# 10_MIPI_LCD_TX2.net
KiCad netlist of a schematic drawn in Altium Designer
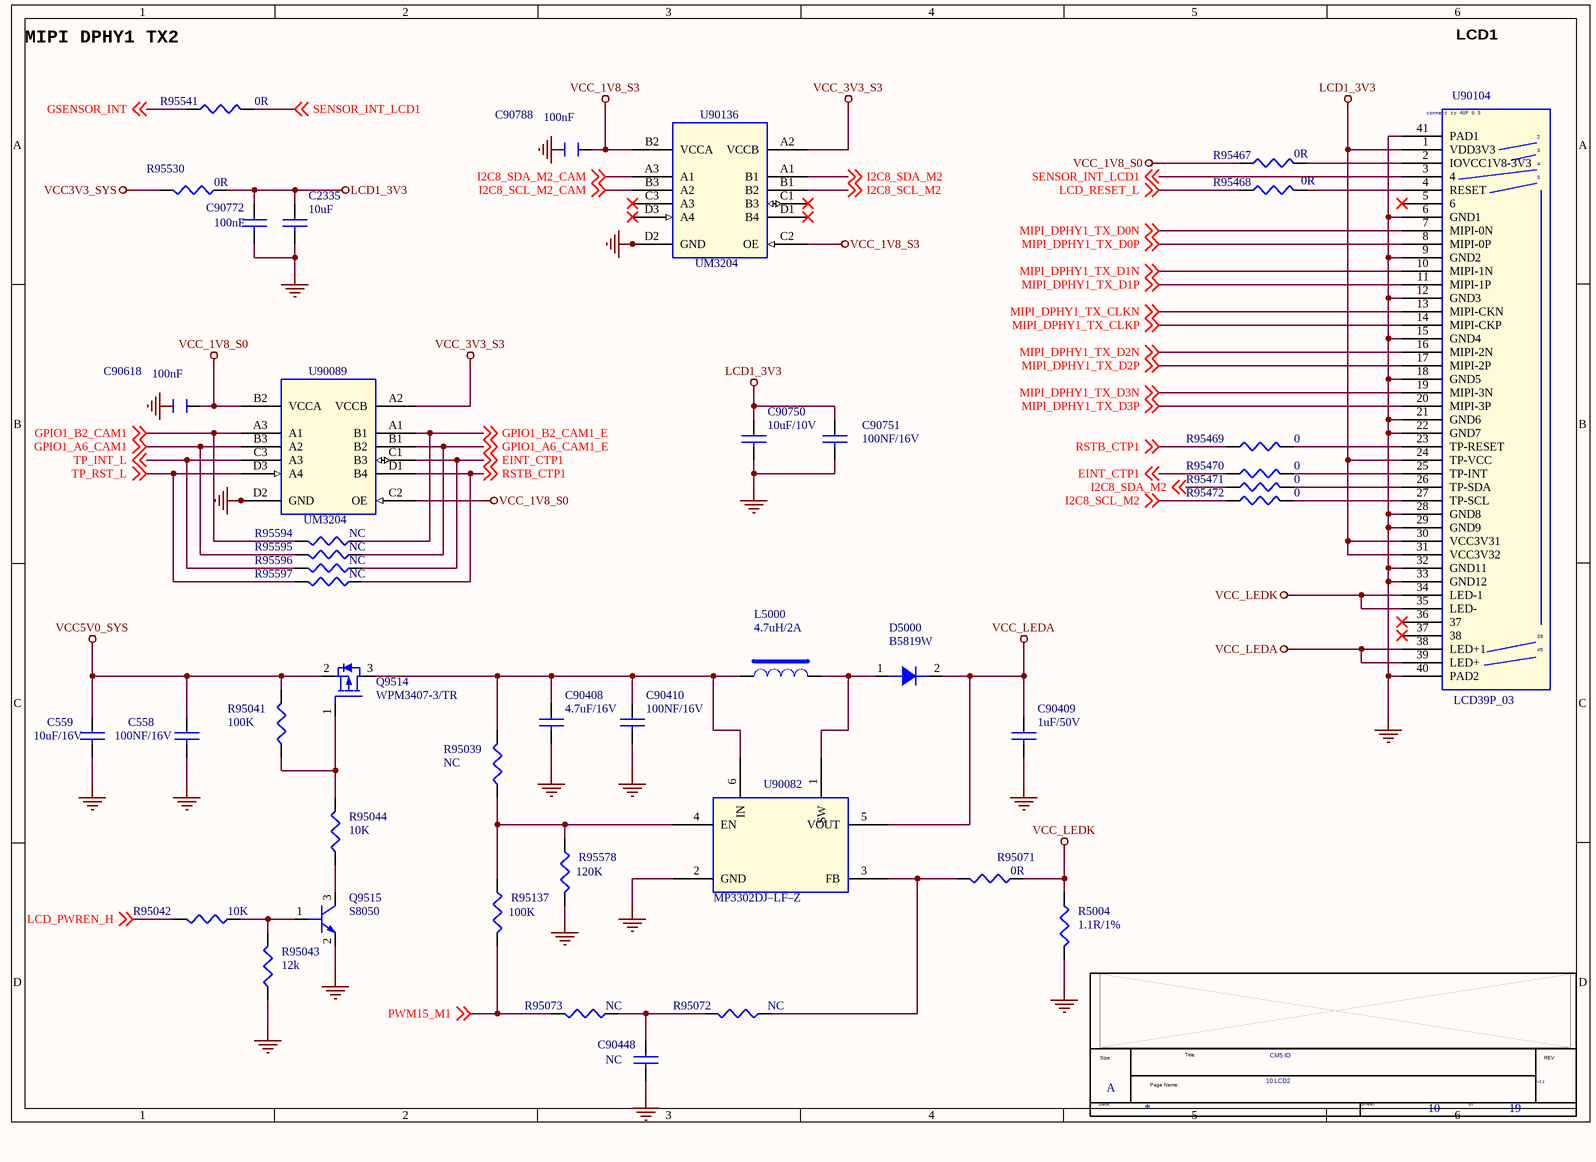
[diagram p0: 10_MIPI_LCD_TX2.SchDoc]

(export (version "E")
  (design (tool "Eeschema 10.0.6"))
  (components
    (comp (ref "*")
      (value "radxa_1010")
      (fields
        (field (name "DOC") "10.LCD2")
        (field (name "REVCODE") "V2.2")
        (field (name "TITLE") "CM5 IO")
        (field (name "PAGE SIZE") "A")
        (field (name "PAGE NUMBER") "10")
        (field (name "PAGE COUNT") "19")
      )
      (libsource (lib "*") (part "radxa_1010"))
    )
    (comp (ref "C558")
      (value "100NF/16V")
      (footprint "C0402")
      (description "cap,100.00nF,+/-10%,16V,X5R,C0402")
      (fields
        (field (name "VOLTAGE") "16V")
        (field (name "TOLERANCE") "10%")
        (field (name "CREATED BY") "JJJ")
      )
      (libsource (lib "*") (part "CAP NP_0_Dup2"))
    )
    (comp (ref "C559")
      (value "10uF/16V")
      (footprint "C0603")
      (description "cap,10.00uF,+/-10%,10V,X5R,C0603")
      (fields
        (field (name "VOLTAGE") "10V")
        (field (name "MANUFACTURER") "TDK")
        (field (name "CREATED BY") "JJJ")
      )
      (libsource (lib "*") (part "CAP NP_0_Dup2"))
    )
    (comp (ref "C2335")
      (value "10uF")
      (footprint "C0603")
      (description "cap,10.00uF,+/-10%,10V,X5R,C0603")
      (fields
        (field (name "VOLTAGE") "10V")
        (field (name "TOLERANCE") "10%")
        (field (name "CREATED BY") "JJJ")
      )
      (libsource (lib "*") (part "CAP NP_0_Dup2"))
    )
    (comp (ref "C90408")
      (value "4.7uF/16V")
      (footprint "C0603")
      (description "cap,4.70uF,+/-10%,10V,X5R,C0603")
      (fields
        (field (name "VOLTAGE") "10V")
        (field (name "TOLERANCE") "10%")
        (field (name "CREATED BY") "JJJ")
      )
      (libsource (lib "*") (part "CAP NP_0_Dup2"))
    )
    (comp (ref "C90409")
      (value "1uF/50V")
      (footprint "C0603")
      (description "cap,2.20uF,+/-10%,35V,X5R,C0603")
      (fields
        (field (name "VOLTAGE") "35V")
        (field (name "TOLERANCE") "10%")
        (field (name "CREATED BY") "JJJ")
      )
      (libsource (lib "*") (part "CAP NP_0_Dup2"))
    )
    (comp (ref "C90410")
      (value "100NF/16V")
      (footprint "C0402")
      (description "cap,100.00nF,+/-10%,16V,X5R,C0402")
      (fields
        (field (name "VOLTAGE") "16V")
        (field (name "TOLERANCE") "10%")
        (field (name "CREATED BY") "JJJ")
      )
      (libsource (lib "*") (part "CAP NP_0_Dup2"))
    )
    (comp (ref "C90448")
      (value "NC")
      (footprint "C0402")
      (description "cap,100.00nF,+/-10%,16V,X5R,C0402")
      (fields
        (field (name "VOLTAGE") "16V")
        (field (name "TOLERANCE") "10%")
        (field (name "CREATED BY") "JJJ")
      )
      (libsource (lib "*") (part "CAP NP_0_Dup2"))
    )
    (comp (ref "C90618") (value "100nF") (footprint "C0402") (libsource (lib "*") (part "CAPACITOR_0")))
    (comp (ref "C90750")
      (value "10uF/10V")
      (footprint "C0603")
      (description "cap,10.00uF,+/-10%,10V,X5R,C0603")
      (fields
        (field (name "VOLTAGE") "10V")
        (field (name "TOLERANCE") "10%")
        (field (name "CREATED BY") "JJJ")
      )
      (libsource (lib "*") (part "CAP NP_0_Dup2"))
    )
    (comp (ref "C90751")
      (value "100NF/16V")
      (footprint "C0402")
      (description "cap,100.00nF,+/-10%,16V,X5R,C0402")
      (fields
        (field (name "VOLTAGE") "16V")
        (field (name "MANUFACTURER") "TDK")
        (field (name "CREATED BY") "JJJ")
      )
      (libsource (lib "*") (part "CAP NP_0_Dup2"))
    )
    (comp (ref "C90772")
      (value "100nF")
      (footprint "C0402")
      (description "cap,100.00nF,+/-10%,16V,X5R,C0402")
      (fields
        (field (name "VOLTAGE") "16V")
        (field (name "TOLERANCE") "10%")
        (field (name "CREATED BY") "JJJ")
      )
      (libsource (lib "*") (part "CAP NP_0_Dup2"))
    )
    (comp (ref "C90788") (value "100nF") (footprint "C0402") (libsource (lib "*") (part "CAPACITOR_0")))
    (comp (ref "D5000")
      (value "B5819W")
      (footprint "SOD_123")
      (description "Schottky Barrier，SS32 DO214AC")
      (fields (field (name "MANUFACTURER") "星海") (field (name "CREATED BY") "JJJ"))
      (libsource (lib "*") (part "DIODE_Dup1"))
    )
    (comp (ref "L5000")
      (value "4.7uH/2A")
      (footprint "IND-303015")
      (description "Power Inductor,4.7uH,0.2,IND_404030")
      (fields
        (field (name "TOLERANCE") "20%")
        (field (name "MANUFACTURER") "sunlord")
        (field (name "CREATED BY") "YTL")
      )
      (libsource (lib "*") (part "INDUCTORS OF FERRITE_Dup1"))
    )
    (comp (ref "Q9514")
      (value "WPM3407-3/TR")
      (footprint "SOT23")
      (description "PMOS,WPM3407-3/TR,SOT_23,Id=4.4A,Vds=30V")
      (fields (field (name "MANUFACTURER") "WillSemi(韦尔半导体)") (field (name "CREATED BY") "JJJ"))
      (libsource (lib "*") (part "MOSFET P"))
    )
    (comp (ref "Q9515")
      (value "S8050")
      (footprint "SOT_23")
      (description "S8050,SOT23")
      (fields (field (name "MANUFACTURER") "长电") (field (name "CREATED BY") "JJJ"))
      (libsource (lib "*") (part "NPN"))
    )
    (comp (ref "R5004")
      (value "1.1R/1%")
      (footprint "R0402")
      (description "通用厚膜电阻,3R9,+/-5%,R1206,1/4W.")
      (fields
        (field (name "TOLERANCE") "5%")
        (field (name "MANUFACTURER") "YAGEO")
        (field (name "CREATED BY") "YTL")
      )
      (libsource (lib "*") (part "RESISTOR_1_Dup1"))
    )
    (comp (ref "R95039")
      (value "NC")
      (footprint "R0402")
      (description "通用厚膜电阻,27K,+/-5%,R0402,1/16W.")
      (fields
        (field (name "TOLERANCE") "5%")
        (field (name "MANUFACTURER") "YAGEO")
        (field (name "CREATED BY") "YTL")
      )
      (libsource (lib "*") (part "RESISTOR_1_Dup1"))
    )
    (comp (ref "R95041")
      (value "100K")
      (footprint "R0402")
      (description "通用厚膜电阻,10K,+/-5%,R0402,1/16W.")
      (fields
        (field (name "TOLERANCE") "5%")
        (field (name "MANUFACTURER") "YAGEO")
        (field (name "CREATED BY") "YTL")
      )
      (libsource (lib "*") (part "RESISTOR_1_Dup1"))
    )
    (comp (ref "R95042")
      (value "10K")
      (footprint "R0402")
      (description "通用厚膜电阻,10K,+/-5%,R0402,1/16W.")
      (fields
        (field (name "TOLERANCE") "5%")
        (field (name "MANUFACTURER") "YAGEO")
        (field (name "CREATED BY") "YTL")
      )
      (libsource (lib "*") (part "RESISTOR_1_Dup1"))
    )
    (comp (ref "R95043")
      (value "12k")
      (footprint "R0402")
      (description "通用厚膜电阻,20K,+/-5%,R0402,1/16W.")
      (fields
        (field (name "TOLERANCE") "5%")
        (field (name "MANUFACTURER") "YAGEO")
        (field (name "CREATED BY") "YTL")
      )
      (libsource (lib "*") (part "RESISTOR_1_Dup1"))
    )
    (comp (ref "R95044")
      (value "10K")
      (footprint "R0402")
      (description "通用厚膜电阻,10K,+/-5%,R0402,1/16W.")
      (fields
        (field (name "TOLERANCE") "5%")
        (field (name "MANUFACTURER") "YAGEO")
        (field (name "CREATED BY") "YTL")
      )
      (libsource (lib "*") (part "RESISTOR_1_Dup1"))
    )
    (comp (ref "R95071")
      (value "0R")
      (footprint "R0402")
      (description "通用厚膜电阻,27K,+/-5%,R0402,1/16W.")
      (fields
        (field (name "TOLERANCE") "5%")
        (field (name "MANUFACTURER") "YAGEO")
        (field (name "CREATED BY") "YTL")
      )
      (libsource (lib "*") (part "RESISTOR_1_Dup1"))
    )
    (comp (ref "R95072")
      (value "NC")
      (footprint "R0402")
      (description "通用厚膜电阻,27K,+/-5%,R0402,1/16W.")
      (fields
        (field (name "TOLERANCE") "5%")
        (field (name "MANUFACTURER") "YAGEO")
        (field (name "CREATED BY") "YTL")
      )
      (libsource (lib "*") (part "RESISTOR_1_Dup1"))
    )
    (comp (ref "R95073")
      (value "NC")
      (footprint "R0402")
      (description "通用厚膜电阻,27K,+/-5%,R0402,1/16W.")
      (fields
        (field (name "TOLERANCE") "5%")
        (field (name "MANUFACTURER") "YAGEO")
        (field (name "CREATED BY") "YTL")
      )
      (libsource (lib "*") (part "RESISTOR_1_Dup1"))
    )
    (comp (ref "R95137")
      (value "100K")
      (footprint "R0402")
      (description "通用厚膜电阻,27K,+/-5%,R0402,1/16W.")
      (fields
        (field (name "TOLERANCE") "5%")
        (field (name "MANUFACTURER") "YAGEO")
        (field (name "CREATED BY") "YTL")
      )
      (libsource (lib "*") (part "RESISTOR_1_Dup1"))
    )
    (comp (ref "R95467")
      (value "0R")
      (footprint "R0402")
      (description "通用厚膜电阻,100K,+/-5%,R0402,1/16W.")
      (fields
        (field (name "TOLERANCE") "5%")
        (field (name "MANUFACTURER") "YAGEO")
        (field (name "CREATED BY") "YTL")
      )
      (libsource (lib "*") (part "RESISTOR_1_Dup1"))
    )
    (comp (ref "R95468")
      (value "0R")
      (footprint "R0402")
      (description "通用厚膜电阻,100K,+/-5%,R0402,1/16W.")
      (fields
        (field (name "TOLERANCE") "5%")
        (field (name "MANUFACTURER") "YAGEO")
        (field (name "CREATED BY") "YTL")
      )
      (libsource (lib "*") (part "RESISTOR_1_Dup1"))
    )
    (comp (ref "R95469") (value "0") (footprint "R0201") (libsource (lib "*") (part "R / 0 / ohm / 0201_0")))
    (comp (ref "R95470") (value "0") (footprint "R0201") (libsource (lib "*") (part "R / 0 / ohm / 0201_0")))
    (comp (ref "R95471") (value "0") (footprint "R0201") (libsource (lib "*") (part "R / 0 / ohm / 0201_0")))
    (comp (ref "R95472") (value "0") (footprint "R0201") (libsource (lib "*") (part "R / 0 / ohm / 0201_0")))
    (comp (ref "R95530")
      (value "0R")
      (footprint "R0402")
      (description "通用厚膜电阻,10K,+/-5%,R0402,1/16W.")
      (fields
        (field (name "TOLERANCE") "5%")
        (field (name "MANUFACTURER") "YAGEO")
        (field (name "CREATED BY") "YTL")
      )
      (libsource (lib "*") (part "RESISTOR_1_Dup1"))
    )
    (comp (ref "R95541")
      (value "0R")
      (footprint "R0402")
      (description "通用厚膜电阻,10K,+/-5%,R0402,1/16W.")
      (fields
        (field (name "TOLERANCE") "5%")
        (field (name "MANUFACTURER") "YAGEO")
        (field (name "CREATED BY") "YTL")
      )
      (libsource (lib "*") (part "RESISTOR_1_Dup1"))
    )
    (comp (ref "R95578")
      (value "120K")
      (footprint "R0402")
      (description "通用厚膜电阻,27K,+/-5%,R0402,1/16W.")
      (fields
        (field (name "TOLERANCE") "5%")
        (field (name "MANUFACTURER") "YAGEO")
        (field (name "CREATED BY") "YTL")
      )
      (libsource (lib "*") (part "RESISTOR_1_Dup1"))
    )
    (comp (ref "R95594")
      (value "NC")
      (footprint "R0402")
      (description "通用厚膜电阻,10K,+/-5%,R0402,1/16W.")
      (fields
        (field (name "TOLERANCE") "5%")
        (field (name "MANUFACTURER") "YAGEO")
        (field (name "CREATED BY") "YTL")
      )
      (libsource (lib "*") (part "RESISTOR_1_Dup1"))
    )
    (comp (ref "R95595")
      (value "NC")
      (footprint "R0402")
      (description "通用厚膜电阻,10K,+/-5%,R0402,1/16W.")
      (fields
        (field (name "TOLERANCE") "5%")
        (field (name "MANUFACTURER") "YAGEO")
        (field (name "CREATED BY") "YTL")
      )
      (libsource (lib "*") (part "RESISTOR_1_Dup1"))
    )
    (comp (ref "R95596")
      (value "NC")
      (footprint "R0402")
      (description "通用厚膜电阻,10K,+/-5%,R0402,1/16W.")
      (fields
        (field (name "TOLERANCE") "5%")
        (field (name "MANUFACTURER") "YAGEO")
        (field (name "CREATED BY") "YTL")
      )
      (libsource (lib "*") (part "RESISTOR_1_Dup1"))
    )
    (comp (ref "R95597")
      (value "NC")
      (footprint "R0402")
      (description "通用厚膜电阻,10K,+/-5%,R0402,1/16W.")
      (fields
        (field (name "TOLERANCE") "5%")
        (field (name "MANUFACTURER") "YAGEO")
        (field (name "CREATED BY") "YTL")
      )
      (libsource (lib "*") (part "RESISTOR_1_Dup1"))
    )
    (comp (ref "U90082")
      (value "MP3302DJ–LF–Z")
      (footprint "sot23-6")
      (libsource (lib "*") (part "MP3302_0"))
    )
    (comp (ref "U90089")
      (value "UM3204")
      (footprint "CSP-12")
      (description "4-bit Bi-directional Level Shifter  UM3204H")
      (fields (field (name "PART NUMBER") "PI4ULS5V104GAEX"))
      (libsource (lib "*") (part "MP2610_0"))
    )
    (comp (ref "U90104")
      (value "LCD39P_03")
      (footprint "LCD39PIN-ok")
      (libsource (lib "*") (part "LCD39P_03"))
    )
    (comp (ref "U90136")
      (value "UM3204")
      (footprint "CSP-12")
      (description "4-bit Bi-directional Level Shifter  UM3204H")
      (fields (field (name "PART NUMBER") "PI4ULS5V104GAEX"))
      (libsource (lib "*") (part "MP2610_0"))
    )
  )
  (nets
    (net (code "1") (name "EINT_CTP1") (class "Default")
      (node (ref "R95470") (pin "1") (pinfunction "1_1") (pintype "passive"))
      (node (ref "R95596") (pin "2") (pinfunction "2_2") (pintype "passive"))
      (node (ref "U90089") (pin "C1") (pinfunction "B3_C1") (pintype "bidirectional"))
    )
    (net (code "2") (name "GND") (class "Default")
      (node (ref "C2335") (pin "2") (pinfunction "2_2") (pintype "passive"))
      (node (ref "C558") (pin "2") (pinfunction "2_2") (pintype "passive"))
      (node (ref "C559") (pin "2") (pinfunction "2_2") (pintype "passive"))
      (node (ref "C90408") (pin "2") (pinfunction "2_2") (pintype "passive"))
      (node (ref "C90409") (pin "2") (pinfunction "2_2") (pintype "passive"))
      (node (ref "C90410") (pin "2") (pinfunction "2_2") (pintype "passive"))
      (node (ref "C90448") (pin "2") (pinfunction "2_2") (pintype "passive"))
      (node (ref "C90750") (pin "2") (pinfunction "2_2") (pintype "passive"))
      (node (ref "C90751") (pin "2") (pinfunction "2_2") (pintype "passive"))
      (node (ref "C90772") (pin "2") (pinfunction "2_2") (pintype "passive"))
      (node (ref "Q9515") (pin "2") (pinfunction "EMITTER_2") (pintype "passive"))
      (node (ref "R5004") (pin "2") (pinfunction "2_2") (pintype "passive"))
      (node (ref "R95043") (pin "2") (pinfunction "2_2") (pintype "passive"))
      (node (ref "R95578") (pin "1") (pinfunction "1_1") (pintype "passive"))
      (node (ref "U90082") (pin "2") (pinfunction "GND_2") (pintype "passive"))
      (node (ref "U90089") (pin "D2") (pinfunction "GND_D2") (pintype "power_in"))
      (node (ref "U90104") (pin "12") (pinfunction "GND3_12") (pintype "passive"))
      (node (ref "U90104") (pin "15") (pinfunction "GND4_15") (pintype "passive"))
      (node (ref "U90104") (pin "18") (pinfunction "GND5_18") (pintype "passive"))
      (node (ref "U90104") (pin "21") (pinfunction "GND6_21") (pintype "passive"))
      (node (ref "U90104") (pin "22") (pinfunction "GND7_22") (pintype "passive"))
      (node (ref "U90104") (pin "28") (pinfunction "GND8_28") (pintype "passive"))
      (node (ref "U90104") (pin "29") (pinfunction "GND9_29") (pintype "passive"))
      (node (ref "U90104") (pin "32") (pinfunction "GND11_32") (pintype "passive"))
      (node (ref "U90104") (pin "33") (pinfunction "GND12_33") (pintype "passive"))
      (node (ref "U90104") (pin "40") (pinfunction "PAD2_40") (pintype "passive"))
      (node (ref "U90104") (pin "41") (pinfunction "PAD1_41") (pintype "passive"))
      (node (ref "U90104") (pin "6") (pinfunction "GND1_6") (pintype "passive"))
      (node (ref "U90104") (pin "9") (pinfunction "GND2_9") (pintype "passive"))
      (node (ref "U90136") (pin "D2") (pinfunction "GND_D2") (pintype "power_in"))
    )
    (net (code "3") (name "GPIO1_A6_CAM1") (class "Default")
      (node (ref "R95595") (pin "1") (pinfunction "1_1") (pintype "passive"))
      (node (ref "U90089") (pin "B3") (pinfunction "A2_B3") (pintype "tri_state"))
    )
    (net (code "4") (name "GPIO1_A6_CAM1_E") (class "Default")
      (node (ref "R95595") (pin "2") (pinfunction "2_2") (pintype "passive"))
      (node (ref "U90089") (pin "B1") (pinfunction "B2_B1") (pintype "tri_state"))
    )
    (net (code "5") (name "GPIO1_B2_CAM1") (class "Default")
      (node (ref "R95594") (pin "1") (pinfunction "1_1") (pintype "passive"))
      (node (ref "U90089") (pin "A3") (pinfunction "A1_A3") (pintype "tri_state"))
    )
    (net (code "6") (name "GPIO1_B2_CAM1_E") (class "Default")
      (node (ref "R95594") (pin "2") (pinfunction "2_2") (pintype "passive"))
      (node (ref "U90089") (pin "A1") (pinfunction "B1_A1") (pintype "tri_state"))
    )
    (net (code "7") (name "GSENSOR_INT") (class "Default")
      (node (ref "R95541") (pin "2") (pinfunction "2_2") (pintype "passive"))
    )
    (net (code "8") (name "I2C8_SCL_M2") (class "Default")
      (node (ref "R95472") (pin "1") (pinfunction "1_1") (pintype "passive"))
      (node (ref "U90136") (pin "B1") (pinfunction "B2_B1") (pintype "tri_state"))
    )
    (net (code "9") (name "I2C8_SCL_M2_CAM") (class "Default")
      (node (ref "U90136") (pin "B3") (pinfunction "A2_B3") (pintype "tri_state"))
    )
    (net (code "10") (name "I2C8_SDA_M2") (class "Default")
      (node (ref "R95471") (pin "1") (pinfunction "1_1") (pintype "passive"))
      (node (ref "U90136") (pin "A1") (pinfunction "B1_A1") (pintype "tri_state"))
    )
    (net (code "11") (name "I2C8_SDA_M2_CAM") (class "Default")
      (node (ref "U90136") (pin "A3") (pinfunction "A1_A3") (pintype "tri_state"))
    )
    (net (code "12") (name "LCD1_3V3") (class "Default")
      (node (ref "C2335") (pin "1") (pinfunction "1_1") (pintype "passive"))
      (node (ref "C90750") (pin "1") (pinfunction "1_1") (pintype "passive"))
      (node (ref "C90751") (pin "1") (pinfunction "1_1") (pintype "passive"))
      (node (ref "C90772") (pin "1") (pinfunction "1_1") (pintype "passive"))
      (node (ref "R95530") (pin "2") (pinfunction "2_2") (pintype "passive"))
      (node (ref "U90104") (pin "1") (pinfunction "VDD3V3_1") (pintype "passive"))
      (node (ref "U90104") (pin "24") (pinfunction "TP-VCC_24") (pintype "passive"))
      (node (ref "U90104") (pin "30") (pinfunction "VCC3V31_30") (pintype "passive"))
      (node (ref "U90104") (pin "31") (pinfunction "VCC3V32_31") (pintype "passive"))
    )
    (net (code "13") (name "LCD_PWREN_H") (class "Default")
      (node (ref "R95042") (pin "1") (pinfunction "1_1") (pintype "passive"))
    )
    (net (code "14") (name "LCD_RESET_L") (class "Default")
      (node (ref "R95468") (pin "1") (pinfunction "1_1") (pintype "passive"))
    )
    (net (code "15") (name "MIPI_DPHY1_TX_CLKN") (class "Default")
      (node (ref "U90104") (pin "13") (pinfunction "MIPI-CKN_13") (pintype "passive"))
    )
    (net (code "16") (name "MIPI_DPHY1_TX_CLKP") (class "Default")
      (node (ref "U90104") (pin "14") (pinfunction "MIPI-CKP_14") (pintype "passive"))
    )
    (net (code "17") (name "MIPI_DPHY1_TX_D0N") (class "Default")
      (node (ref "U90104") (pin "7") (pinfunction "MIPI-0N_7") (pintype "passive"))
    )
    (net (code "18") (name "MIPI_DPHY1_TX_D0P") (class "Default")
      (node (ref "U90104") (pin "8") (pinfunction "MIPI-0P_8") (pintype "passive"))
    )
    (net (code "19") (name "MIPI_DPHY1_TX_D1N") (class "Default")
      (node (ref "U90104") (pin "10") (pinfunction "MIPI-1N_10") (pintype "passive"))
    )
    (net (code "20") (name "MIPI_DPHY1_TX_D1P") (class "Default")
      (node (ref "U90104") (pin "11") (pinfunction "MIPI-1P_11") (pintype "passive"))
    )
    (net (code "21") (name "MIPI_DPHY1_TX_D2N") (class "Default")
      (node (ref "U90104") (pin "16") (pinfunction "MIPI-2N_16") (pintype "passive"))
    )
    (net (code "22") (name "MIPI_DPHY1_TX_D2P") (class "Default")
      (node (ref "U90104") (pin "17") (pinfunction "MIPI-2P_17") (pintype "passive"))
    )
    (net (code "23") (name "MIPI_DPHY1_TX_D3N") (class "Default")
      (node (ref "U90104") (pin "19") (pinfunction "MIPI-3N_19") (pintype "passive"))
    )
    (net (code "24") (name "MIPI_DPHY1_TX_D3P") (class "Default")
      (node (ref "U90104") (pin "20") (pinfunction "MIPI-3P_20") (pintype "passive"))
    )
    (net (code "25") (name "Net-(C90448-Pad1)") (class "Default")
      (node (ref "C90448") (pin "1") (pinfunction "1_1") (pintype "passive"))
      (node (ref "R95072") (pin "1") (pinfunction "1_1") (pintype "passive"))
      (node (ref "R95073") (pin "2") (pinfunction "2_2") (pintype "passive"))
    )
    (net (code "26") (name "Net-(D5000-A)") (class "Default")
      (node (ref "D5000") (pin "1") (pinfunction "A_1") (pintype "passive"))
      (node (ref "L5000") (pin "2") (pinfunction "2_2") (pintype "passive"))
      (node (ref "U90082") (pin "1") (pinfunction "SW_1") (pintype "passive"))
    )
    (net (code "27") (name "Net-(Q9514-DRAIN)") (class "Default")
      (node (ref "C90408") (pin "1") (pinfunction "1_1") (pintype "passive"))
      (node (ref "C90410") (pin "1") (pinfunction "1_1") (pintype "passive"))
      (node (ref "L5000") (pin "1") (pinfunction "1_1") (pintype "passive"))
      (node (ref "Q9514") (pin "3") (pinfunction "DRAIN_3") (pintype "passive"))
      (node (ref "R95039") (pin "1") (pinfunction "1_1") (pintype "passive"))
      (node (ref "U90082") (pin "6") (pinfunction "IN_6") (pintype "passive"))
    )
    (net (code "28") (name "Net-(Q9514-GATE)") (class "Default")
      (node (ref "Q9514") (pin "1") (pinfunction "GATE_1") (pintype "passive"))
      (node (ref "R95041") (pin "2") (pinfunction "2_2") (pintype "passive"))
      (node (ref "R95044") (pin "1") (pinfunction "1_1") (pintype "passive"))
    )
    (net (code "29") (name "Net-(Q9515-BASE)") (class "Default")
      (node (ref "Q9515") (pin "1") (pinfunction "BASE_1") (pintype "passive"))
      (node (ref "R95042") (pin "2") (pinfunction "2_2") (pintype "passive"))
      (node (ref "R95043") (pin "1") (pinfunction "1_1") (pintype "passive"))
    )
    (net (code "30") (name "Net-(Q9515-COLLECTOR)") (class "Default")
      (node (ref "Q9515") (pin "3") (pinfunction "COLLECTOR_3") (pintype "passive"))
      (node (ref "R95044") (pin "2") (pinfunction "2_2") (pintype "passive"))
    )
    (net (code "31") (name "Net-(U90082-EN)") (class "Default")
      (node (ref "R95039") (pin "2") (pinfunction "2_2") (pintype "passive"))
      (node (ref "R95137") (pin "2") (pinfunction "2_2") (pintype "passive"))
      (node (ref "R95578") (pin "2") (pinfunction "2_2") (pintype "passive"))
      (node (ref "U90082") (pin "4") (pinfunction "EN_4") (pintype "passive"))
    )
    (net (code "32") (name "Net-(U90082-FB)") (class "Default")
      (node (ref "R95071") (pin "1") (pinfunction "1_1") (pintype "passive"))
      (node (ref "R95072") (pin "2") (pinfunction "2_2") (pintype "passive"))
      (node (ref "U90082") (pin "3") (pinfunction "FB_3") (pintype "passive"))
    )
    (net (code "33") (name "Net-(U90104-IOVCC1V8-3V3)") (class "Default")
      (node (ref "R95467") (pin "2") (pinfunction "2_2") (pintype "passive"))
      (node (ref "U90104") (pin "2") (pinfunction "IOVCC1V8-3V3_2") (pintype "passive"))
    )
    (net (code "34") (name "Net-(U90104-RESET)") (class "Default")
      (node (ref "R95468") (pin "2") (pinfunction "2_2") (pintype "passive"))
      (node (ref "U90104") (pin "4") (pinfunction "RESET_4") (pintype "passive"))
    )
    (net (code "35") (name "Net-(U90104-TP-INT)") (class "Default")
      (node (ref "R95470") (pin "2") (pinfunction "2_2") (pintype "passive"))
      (node (ref "U90104") (pin "25") (pinfunction "TP-INT_25") (pintype "passive"))
    )
    (net (code "36") (name "Net-(U90104-TP-RESET)") (class "Default")
      (node (ref "R95469") (pin "2") (pinfunction "2_2") (pintype "passive"))
      (node (ref "U90104") (pin "23") (pinfunction "TP-RESET_23") (pintype "passive"))
    )
    (net (code "37") (name "Net-(U90104-TP-SCL)") (class "Default")
      (node (ref "R95472") (pin "2") (pinfunction "2_2") (pintype "passive"))
      (node (ref "U90104") (pin "27") (pinfunction "TP-SCL_27") (pintype "passive"))
    )
    (net (code "38") (name "Net-(U90104-TP-SDA)") (class "Default")
      (node (ref "R95471") (pin "2") (pinfunction "2_2") (pintype "passive"))
      (node (ref "U90104") (pin "26") (pinfunction "TP-SDA_26") (pintype "passive"))
    )
    (net (code "39") (name "PWM15_M1") (class "Default")
      (node (ref "R95073") (pin "1") (pinfunction "1_1") (pintype "passive"))
      (node (ref "R95137") (pin "1") (pinfunction "1_1") (pintype "passive"))
    )
    (net (code "40") (name "RSTB_CTP1") (class "Default")
      (node (ref "R95469") (pin "1") (pinfunction "1_1") (pintype "passive"))
      (node (ref "R95597") (pin "2") (pinfunction "2_2") (pintype "passive"))
      (node (ref "U90089") (pin "D1") (pinfunction "B4_D1") (pintype "tri_state"))
    )
    (net (code "41") (name "SENSOR_INT_LCD1") (class "Default")
      (node (ref "R95541") (pin "1") (pinfunction "1_1") (pintype "passive"))
      (node (ref "U90104") (pin "3") (pinfunction "4_3") (pintype "passive"))
    )
    (net (code "42") (name "TP_INT_L") (class "Default")
      (node (ref "R95596") (pin "1") (pinfunction "1_1") (pintype "passive"))
      (node (ref "U90089") (pin "C3") (pinfunction "A3_C3") (pintype "tri_state"))
    )
    (net (code "43") (name "TP_RST_L") (class "Default")
      (node (ref "R95597") (pin "1") (pinfunction "1_1") (pintype "passive"))
      (node (ref "U90089") (pin "D3") (pinfunction "A4_D3") (pintype "input"))
    )
    (net (code "44") (name "VCC3V3_SYS") (class "Default")
      (node (ref "R95530") (pin "1") (pinfunction "1_1") (pintype "passive"))
    )
    (net (code "45") (name "VCC5V0_SYS") (class "Default")
      (node (ref "C558") (pin "1") (pinfunction "1_1") (pintype "passive"))
      (node (ref "C559") (pin "1") (pinfunction "1_1") (pintype "passive"))
      (node (ref "Q9514") (pin "2") (pinfunction "SOURCE_2") (pintype "passive"))
      (node (ref "R95041") (pin "1") (pinfunction "1_1") (pintype "passive"))
    )
    (net (code "46") (name "VCC_1V8_S0") (class "Default")
      (node (ref "C90618") (pin "2") (pinfunction "2_2") (pintype "passive"))
      (node (ref "R95467") (pin "1") (pinfunction "1_1") (pintype "passive"))
      (node (ref "U90089") (pin "B2") (pinfunction "VCCA_B2") (pintype "power_in"))
      (node (ref "U90089") (pin "C2") (pinfunction "OE_C2") (pintype "input"))
    )
    (net (code "47") (name "VCC_1V8_S3") (class "Default")
      (node (ref "C90788") (pin "2") (pinfunction "2_2") (pintype "passive"))
      (node (ref "U90136") (pin "B2") (pinfunction "VCCA_B2") (pintype "power_in"))
      (node (ref "U90136") (pin "C2") (pinfunction "OE_C2") (pintype "input"))
    )
    (net (code "48") (name "VCC_3V3_S3") (class "Default")
      (node (ref "U90089") (pin "A2") (pinfunction "VCCB_A2") (pintype "power_in"))
      (node (ref "U90136") (pin "A2") (pinfunction "VCCB_A2") (pintype "power_in"))
    )
    (net (code "49") (name "VCC_LEDA") (class "Default")
      (node (ref "C90409") (pin "1") (pinfunction "1_1") (pintype "passive"))
      (node (ref "D5000") (pin "2") (pinfunction "K_2") (pintype "passive"))
      (node (ref "U90082") (pin "5") (pinfunction "VOUT_5") (pintype "passive"))
      (node (ref "U90104") (pin "38") (pinfunction "LED+1_38") (pintype "passive"))
      (node (ref "U90104") (pin "39") (pinfunction "LED+_39") (pintype "passive"))
    )
    (net (code "50") (name "VCC_LEDK") (class "Default")
      (node (ref "R5004") (pin "1") (pinfunction "1_1") (pintype "passive"))
      (node (ref "R95071") (pin "2") (pinfunction "2_2") (pintype "passive"))
      (node (ref "U90104") (pin "34") (pinfunction "LED-1_34") (pintype "passive"))
      (node (ref "U90104") (pin "35") (pinfunction "LED-_35") (pintype "passive"))
    )
    (net (code "51") (name "unconnected-(C90618-Pad1)") (class "Default")
      (node (ref "C90618") (pin "1") (pinfunction "1_1") (pintype "passive"))
    )
    (net (code "52") (name "unconnected-(C90788-Pad1)") (class "Default")
      (node (ref "C90788") (pin "1") (pinfunction "1_1") (pintype "passive"))
    )
    (net (code "53") (name "unconnected-(U90104-6-Pad5)") (class "Default")
      (node (ref "U90104") (pin "5") (pinfunction "6_5") (pintype "passive+no_connect"))
    )
    (net (code "54") (name "unconnected-(U90104-37-Pad36)") (class "Default")
      (node (ref "U90104") (pin "36") (pinfunction "37_36") (pintype "passive+no_connect"))
    )
    (net (code "55") (name "unconnected-(U90104-38-Pad37)") (class "Default")
      (node (ref "U90104") (pin "37") (pinfunction "38_37") (pintype "passive+no_connect"))
    )
    (net (code "56") (name "unconnected-(U90136-A3-PadC3)") (class "Default")
      (node (ref "U90136") (pin "C3") (pinfunction "A3_C3") (pintype "tri_state+no_connect"))
    )
    (net (code "57") (name "unconnected-(U90136-A4-PadD3)") (class "Default")
      (node (ref "U90136") (pin "D3") (pinfunction "A4_D3") (pintype "input+no_connect"))
    )
    (net (code "58") (name "unconnected-(U90136-B3-PadC1)") (class "Default")
      (node (ref "U90136") (pin "C1") (pinfunction "B3_C1") (pintype "bidirectional+no_connect"))
    )
    (net (code "59") (name "unconnected-(U90136-B4-PadD1)") (class "Default")
      (node (ref "U90136") (pin "D1") (pinfunction "B4_D1") (pintype "tri_state+no_connect"))
    )
  )
)
